# net.net
KiCad netlist of a schematic drawn in EAGLE
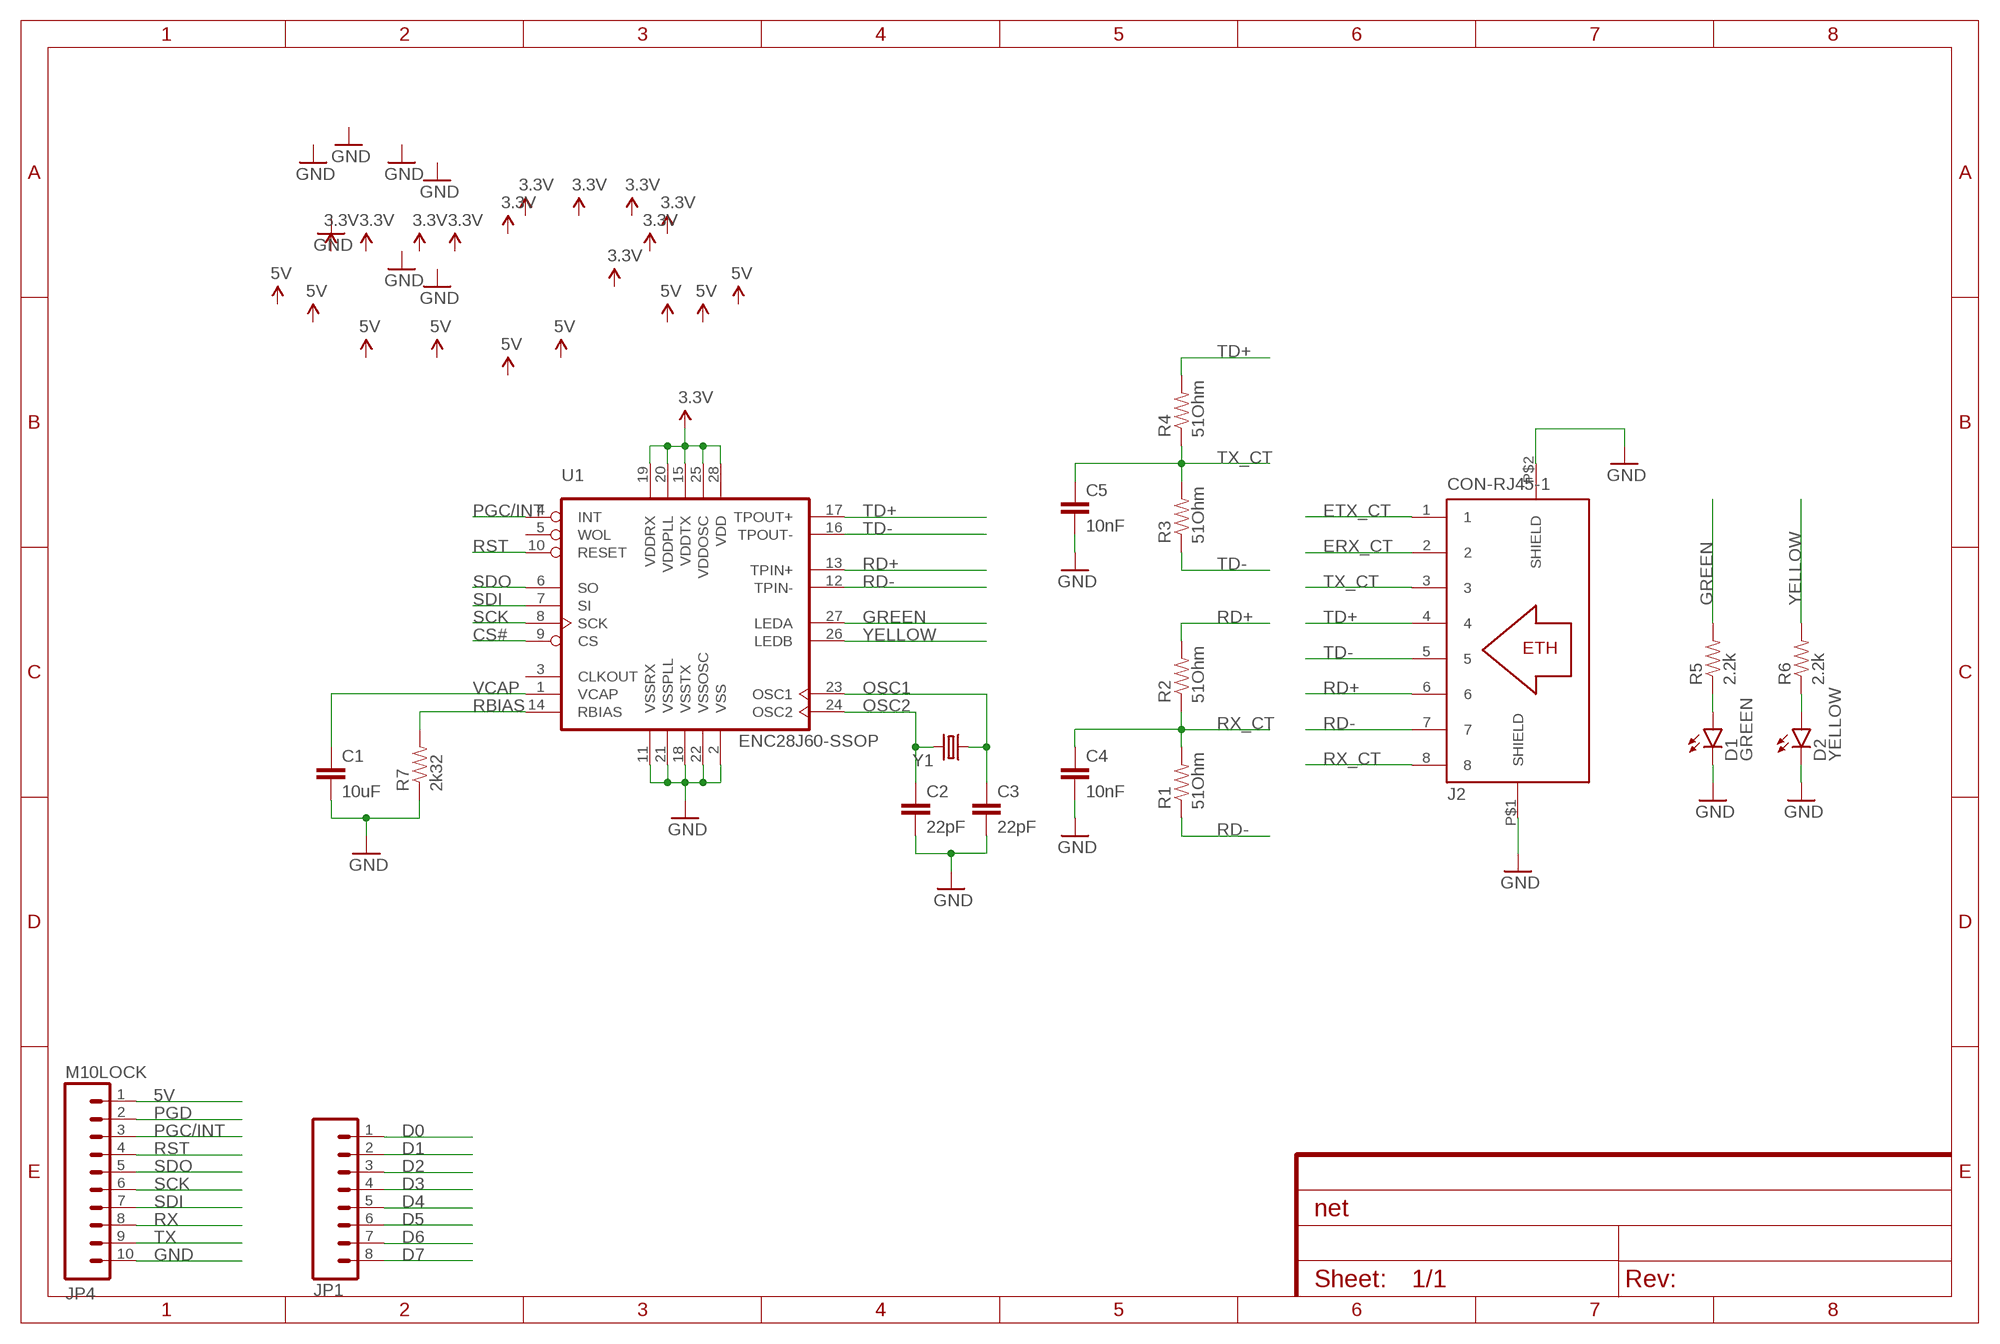
[diagram p0: schematic, sheet 1]

(export (version "E")
  (design (tool "Eeschema 10.0.6"))
  (components
    (comp (ref "C1")
      (value "10uF")
      (footprint "eagle-import:0603-CAP")
      (libsource (lib "eagle-import") (part "10UF-6.3V-20%(0603)"))
    )
    (comp (ref "C2")
      (value "22pF")
      (footprint "eagle-import:0603-CAP")
      (libsource (lib "eagle-import") (part "22PF-50V-5%(0603)"))
    )
    (comp (ref "C3")
      (value "22pF")
      (footprint "eagle-import:0603-CAP")
      (libsource (lib "eagle-import") (part "22PF-50V-5%(0603)"))
    )
    (comp (ref "C4")
      (value "10nF")
      (footprint "eagle-import:0603-CAP")
      (libsource (lib "eagle-import") (part "10NF/10000PF-50V-10%(0603)"))
    )
    (comp (ref "C5")
      (value "10nF")
      (footprint "eagle-import:0603-CAP")
      (libsource (lib "eagle-import") (part "10NF/10000PF-50V-10%(0603)"))
    )
    (comp (ref "D1")
      (value "GREEN")
      (footprint "eagle-import:LED-0603")
      (libsource (lib "eagle-import") (part "LED-RED0603"))
    )
    (comp (ref "D2")
      (value "YELLOW")
      (footprint "eagle-import:LED-0603")
      (libsource (lib "eagle-import") (part "LED-RED0603"))
    )
    (comp (ref "J2")
      (value "CON-RJ45-1")
      (footprint "eagle-import:GM-SMT2-S2-88")
      (libsource (lib "eagle-import") (part "CON-RJ45-1"))
    )
    (comp (ref "JP1")
      (value "M08LOCK")
      (footprint "eagle-import:1X08_LOCK")
      (libsource (lib "eagle-import") (part "M08LOCK"))
    )
    (comp (ref "JP4")
      (value "M10LOCK")
      (footprint "eagle-import:1X10_LOCK")
      (libsource (lib "eagle-import") (part "M10LOCK"))
    )
    (comp (ref "R1")
      (value "51Ohm")
      (footprint "eagle-import:0603")
      (libsource (lib "eagle-import") (part "33OHM1/10W1%(0603)"))
    )
    (comp (ref "R2")
      (value "51Ohm")
      (footprint "eagle-import:0603")
      (libsource (lib "eagle-import") (part "33OHM1/10W1%(0603)"))
    )
    (comp (ref "R3")
      (value "51Ohm")
      (footprint "eagle-import:0603")
      (libsource (lib "eagle-import") (part "33OHM1/10W1%(0603)"))
    )
    (comp (ref "R4")
      (value "51Ohm")
      (footprint "eagle-import:0603")
      (libsource (lib "eagle-import") (part "33OHM1/10W1%(0603)"))
    )
    (comp (ref "R5")
      (value "2.2k")
      (footprint "eagle-import:0603-RES")
      (libsource (lib "eagle-import") (part "2.2KOHM1/10W1%(0603)"))
    )
    (comp (ref "R6")
      (value "2.2k")
      (footprint "eagle-import:0603-RES")
      (libsource (lib "eagle-import") (part "2.2KOHM1/10W1%(0603)"))
    )
    (comp (ref "R7")
      (value "2k32")
      (footprint "eagle-import:0603-RES")
      (libsource (lib "eagle-import") (part "2.2KOHM1/10W1%(0603)"))
    )
    (comp (ref "U1")
      (value "ENC28J60-SSOP")
      (footprint "eagle-import:SSOP28")
      (libsource (lib "eagle-import") (part "ENC28J60-SSOP"))
    )
    (comp (ref "Y1")
      (value "CRYSTAL5X3")
      (footprint "eagle-import:CRYSTAL-SMD-5X3")
      (libsource (lib "eagle-import") (part "CRYSTAL5X3"))
    )
  )
  (nets
    (net (code "1") (name "/CS#") (class "Default")
      (node (ref "U1") (pin "9") (pinfunction "CS_9") (pintype "input"))
    )
    (net (code "2") (name "/D0") (class "Default")
      (node (ref "JP1") (pin "1") (pinfunction "1_1") (pintype "passive"))
    )
    (net (code "3") (name "/D1") (class "Default")
      (node (ref "JP1") (pin "2") (pinfunction "2_2") (pintype "passive"))
    )
    (net (code "4") (name "/D2") (class "Default")
      (node (ref "JP1") (pin "3") (pinfunction "3_3") (pintype "passive"))
    )
    (net (code "5") (name "/D3") (class "Default")
      (node (ref "JP1") (pin "4") (pinfunction "4_4") (pintype "passive"))
    )
    (net (code "6") (name "/D4") (class "Default")
      (node (ref "JP1") (pin "5") (pinfunction "5_5") (pintype "passive"))
    )
    (net (code "7") (name "/D5") (class "Default")
      (node (ref "JP1") (pin "6") (pinfunction "6_6") (pintype "passive"))
    )
    (net (code "8") (name "/D6") (class "Default")
      (node (ref "JP1") (pin "7") (pinfunction "7_7") (pintype "passive"))
    )
    (net (code "9") (name "/D7") (class "Default")
      (node (ref "JP1") (pin "8") (pinfunction "8_8") (pintype "passive"))
    )
    (net (code "10") (name "/ERX_CT") (class "Default")
      (node (ref "J2") (pin "2") (pinfunction "2_2") (pintype "passive"))
    )
    (net (code "11") (name "/ETX_CT") (class "Default")
      (node (ref "J2") (pin "1") (pinfunction "1_1") (pintype "passive"))
    )
    (net (code "12") (name "/GREEN") (class "Default")
      (node (ref "R5") (pin "2") (pinfunction "2_2") (pintype "passive"))
      (node (ref "U1") (pin "27") (pinfunction "LEDA_27") (pintype "output"))
    )
    (net (code "13") (name "/OSC1") (class "Default")
      (node (ref "C3") (pin "1") (pinfunction "1_1") (pintype "passive"))
      (node (ref "U1") (pin "23") (pinfunction "OSC1_23") (pintype "input"))
      (node (ref "Y1") (pin "1") (pinfunction "1_1") (pintype "passive"))
    )
    (net (code "14") (name "/OSC2") (class "Default")
      (node (ref "C2") (pin "1") (pinfunction "1_1") (pintype "passive"))
      (node (ref "U1") (pin "24") (pinfunction "OSC2_24") (pintype "output"))
      (node (ref "Y1") (pin "3") (pinfunction "2_3") (pintype "passive"))
    )
    (net (code "15") (name "/PGC{slash}INT") (class "Default")
      (node (ref "JP4") (pin "3") (pinfunction "3_3") (pintype "passive"))
      (node (ref "U1") (pin "4") (pinfunction "INT_4") (pintype "output"))
    )
    (net (code "16") (name "/PGD") (class "Default")
      (node (ref "JP4") (pin "2") (pinfunction "2_2") (pintype "passive"))
    )
    (net (code "17") (name "/RBIAS") (class "Default")
      (node (ref "R7") (pin "2") (pinfunction "2_2") (pintype "passive"))
      (node (ref "U1") (pin "14") (pinfunction "RBIAS_14") (pintype "passive"))
    )
    (net (code "18") (name "/RD+") (class "Default")
      (node (ref "J2") (pin "6") (pinfunction "6_6") (pintype "passive"))
      (node (ref "R2") (pin "2") (pinfunction "2_2") (pintype "passive"))
      (node (ref "U1") (pin "13") (pinfunction "TPIN+_13") (pintype "input"))
    )
    (net (code "19") (name "/RD-") (class "Default")
      (node (ref "J2") (pin "7") (pinfunction "7_7") (pintype "passive"))
      (node (ref "R1") (pin "1") (pinfunction "1_1") (pintype "passive"))
      (node (ref "U1") (pin "12") (pinfunction "TPIN-_12") (pintype "input"))
    )
    (net (code "20") (name "/RST") (class "Default")
      (node (ref "JP4") (pin "4") (pinfunction "4_4") (pintype "passive"))
      (node (ref "U1") (pin "10") (pinfunction "RESET_10") (pintype "input"))
    )
    (net (code "21") (name "/RX") (class "Default")
      (node (ref "JP4") (pin "8") (pinfunction "8_8") (pintype "passive"))
    )
    (net (code "22") (name "/RX_CT") (class "Default")
      (node (ref "C4") (pin "1") (pinfunction "1_1") (pintype "passive"))
      (node (ref "J2") (pin "8") (pinfunction "8_8") (pintype "passive"))
      (node (ref "R1") (pin "2") (pinfunction "2_2") (pintype "passive"))
      (node (ref "R2") (pin "1") (pinfunction "1_1") (pintype "passive"))
    )
    (net (code "23") (name "/SCK") (class "Default")
      (node (ref "JP4") (pin "6") (pinfunction "6_6") (pintype "passive"))
      (node (ref "U1") (pin "8") (pinfunction "SCK_8") (pintype "input"))
    )
    (net (code "24") (name "/SDI") (class "Default")
      (node (ref "JP4") (pin "7") (pinfunction "7_7") (pintype "passive"))
      (node (ref "U1") (pin "7") (pinfunction "SI_7") (pintype "input"))
    )
    (net (code "25") (name "/SDO") (class "Default")
      (node (ref "JP4") (pin "5") (pinfunction "5_5") (pintype "passive"))
      (node (ref "U1") (pin "6") (pinfunction "SO_6") (pintype "output"))
    )
    (net (code "26") (name "/TD+") (class "Default")
      (node (ref "J2") (pin "4") (pinfunction "4_4") (pintype "passive"))
      (node (ref "R4") (pin "2") (pinfunction "2_2") (pintype "passive"))
      (node (ref "U1") (pin "17") (pinfunction "TPOUT+_17") (pintype "output"))
    )
    (net (code "27") (name "/TD-") (class "Default")
      (node (ref "J2") (pin "5") (pinfunction "5_5") (pintype "passive"))
      (node (ref "R3") (pin "1") (pinfunction "1_1") (pintype "passive"))
      (node (ref "U1") (pin "16") (pinfunction "TPOUT-_16") (pintype "output"))
    )
    (net (code "28") (name "/TX") (class "Default")
      (node (ref "JP4") (pin "9") (pinfunction "9_9") (pintype "passive"))
    )
    (net (code "29") (name "/TX_CT") (class "Default")
      (node (ref "C5") (pin "1") (pinfunction "1_1") (pintype "passive"))
      (node (ref "J2") (pin "3") (pinfunction "3_3") (pintype "passive"))
      (node (ref "R3") (pin "2") (pinfunction "2_2") (pintype "passive"))
      (node (ref "R4") (pin "1") (pinfunction "1_1") (pintype "passive"))
    )
    (net (code "30") (name "/VCAP") (class "Default")
      (node (ref "C1") (pin "1") (pinfunction "1_1") (pintype "passive"))
      (node (ref "U1") (pin "1") (pinfunction "VCAP_1") (pintype "power_in"))
    )
    (net (code "31") (name "/YELLOW") (class "Default")
      (node (ref "R6") (pin "2") (pinfunction "2_2") (pintype "passive"))
      (node (ref "U1") (pin "26") (pinfunction "LEDB_26") (pintype "output"))
    )
    (net (code "32") (name "3.3V") (class "Default")
      (node (ref "U1") (pin "15") (pinfunction "VDDTX_15") (pintype "power_in"))
      (node (ref "U1") (pin "19") (pinfunction "VDDRX_19") (pintype "power_in"))
      (node (ref "U1") (pin "20") (pinfunction "VDDPLL_20") (pintype "power_in"))
      (node (ref "U1") (pin "25") (pinfunction "VDDOSC_25") (pintype "power_in"))
      (node (ref "U1") (pin "28") (pinfunction "VDD_28") (pintype "power_in"))
    )
    (net (code "33") (name "5V") (class "Default")
      (node (ref "JP4") (pin "1") (pinfunction "1_1") (pintype "passive"))
    )
    (net (code "34") (name "GND") (class "Default")
      (node (ref "C1") (pin "2") (pinfunction "2_2") (pintype "passive"))
      (node (ref "C2") (pin "2") (pinfunction "2_2") (pintype "passive"))
      (node (ref "C3") (pin "2") (pinfunction "2_2") (pintype "passive"))
      (node (ref "C4") (pin "2") (pinfunction "2_2") (pintype "passive"))
      (node (ref "C5") (pin "2") (pinfunction "2_2") (pintype "passive"))
      (node (ref "D1") (pin "C") (pinfunction "C_C") (pintype "passive"))
      (node (ref "D2") (pin "C") (pinfunction "C_C") (pintype "passive"))
      (node (ref "J2") (pin "P$1") (pinfunction "SHIELD_P$1") (pintype "passive"))
      (node (ref "J2") (pin "P$2") (pinfunction "SHIELD_P$2") (pintype "passive"))
      (node (ref "JP4") (pin "10") (pinfunction "10_10") (pintype "passive"))
      (node (ref "R7") (pin "1") (pinfunction "1_1") (pintype "passive"))
      (node (ref "U1") (pin "11") (pinfunction "VSSRX_11") (pintype "power_in"))
      (node (ref "U1") (pin "18") (pinfunction "VSSTX_18") (pintype "power_in"))
      (node (ref "U1") (pin "2") (pinfunction "VSS_2") (pintype "power_in"))
      (node (ref "U1") (pin "21") (pinfunction "VSSPLL_21") (pintype "power_in"))
      (node (ref "U1") (pin "22") (pinfunction "VSSOSC_22") (pintype "power_in"))
    )
    (net (code "35") (name "Net-(D1-PadA)") (class "Default")
      (node (ref "D1") (pin "A") (pinfunction "A_A") (pintype "passive"))
      (node (ref "R5") (pin "1") (pinfunction "1_1") (pintype "passive"))
    )
    (net (code "36") (name "Net-(D2-PadA)") (class "Default")
      (node (ref "D2") (pin "A") (pinfunction "A_A") (pintype "passive"))
      (node (ref "R6") (pin "1") (pinfunction "1_1") (pintype "passive"))
    )
    (net (code "37") (name "unconnected-(U1-CLKOUT-Pad3)") (class "Default")
      (node (ref "U1") (pin "3") (pinfunction "CLKOUT_3") (pintype "output"))
    )
    (net (code "38") (name "unconnected-(U1-WOL-Pad5)") (class "Default")
      (node (ref "U1") (pin "5") (pinfunction "WOL_5") (pintype "output"))
    )
  )
)
